# LQFP100_Breakout.net
KiCad netlist of a schematic drawn in EAGLE
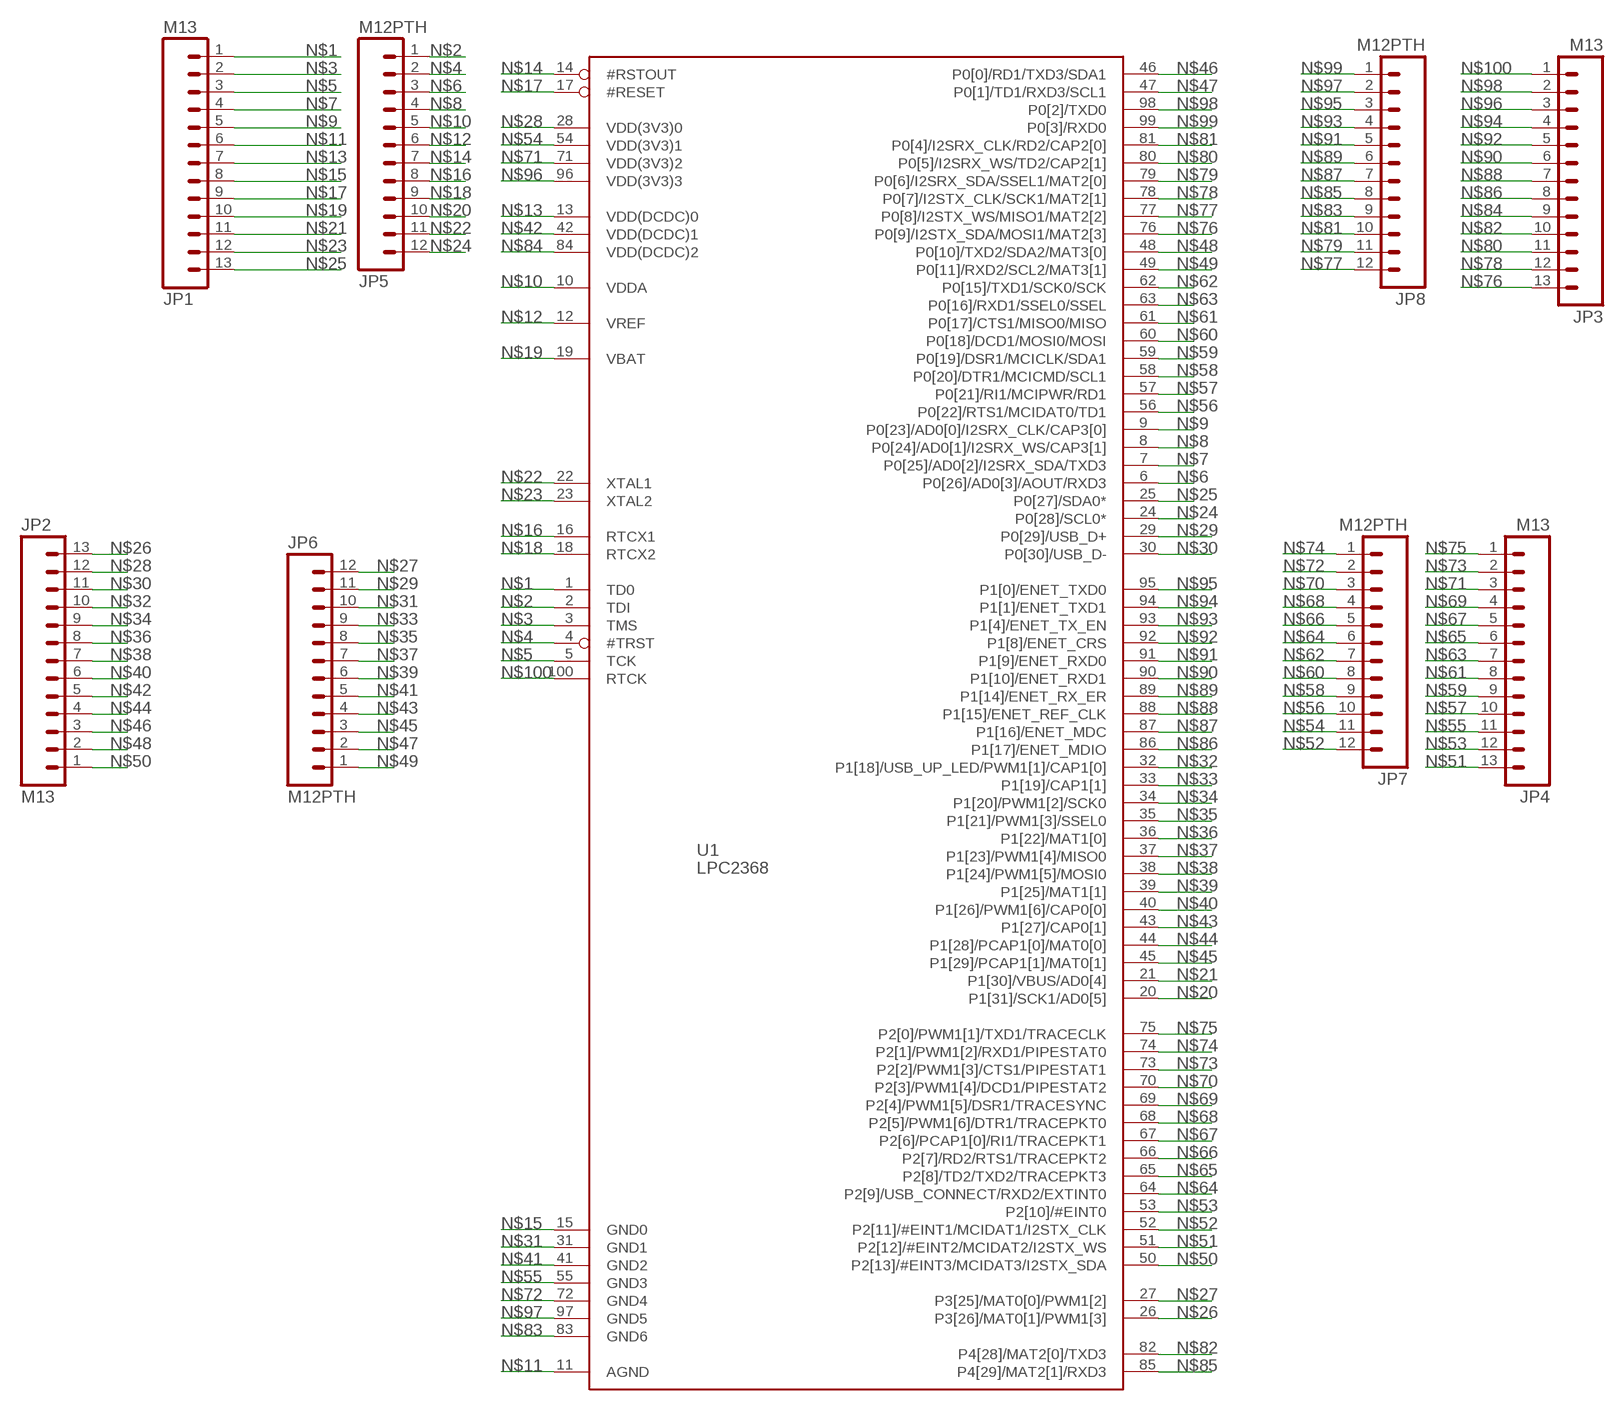
[diagram p0: schematic, sheet 1]

(export (version "E")
  (design (tool "Eeschema 10.0.6"))
  (components
    (comp (ref "JP1")
      (value "M13")
      (footprint "eagle-import:1X13")
      (libsource (lib "eagle-import") (part "M13"))
    )
    (comp (ref "JP2")
      (value "M13")
      (footprint "eagle-import:1X13")
      (libsource (lib "eagle-import") (part "M13"))
    )
    (comp (ref "JP3")
      (value "M13")
      (footprint "eagle-import:1X13")
      (libsource (lib "eagle-import") (part "M13"))
    )
    (comp (ref "JP4")
      (value "M13")
      (footprint "eagle-import:1X13")
      (libsource (lib "eagle-import") (part "M13"))
    )
    (comp (ref "JP5")
      (value "M12PTH")
      (footprint "eagle-import:1X12")
      (libsource (lib "eagle-import") (part "M12PTH"))
    )
    (comp (ref "JP6")
      (value "M12PTH")
      (footprint "eagle-import:1X12")
      (libsource (lib "eagle-import") (part "M12PTH"))
    )
    (comp (ref "JP7")
      (value "M12PTH")
      (footprint "eagle-import:1X12")
      (libsource (lib "eagle-import") (part "M12PTH"))
    )
    (comp (ref "JP8")
      (value "M12PTH")
      (footprint "eagle-import:1X12")
      (libsource (lib "eagle-import") (part "M12PTH"))
    )
    (comp (ref "U1")
      (value "LPC2368")
      (footprint "eagle-import:LQFP100")
      (libsource (lib "eagle-import") (part "LPC2368"))
    )
  )
  (nets
    (net (code "1") (name "/N$1") (class "Default")
      (node (ref "JP1") (pin "1") (pinfunction "1_1") (pintype "passive"))
      (node (ref "U1") (pin "1") (pinfunction "TD0_1") (pintype "bidirectional"))
    )
    (net (code "2") (name "/N$2") (class "Default")
      (node (ref "JP5") (pin "1") (pinfunction "1_1") (pintype "passive"))
      (node (ref "U1") (pin "2") (pinfunction "TDI_2") (pintype "bidirectional"))
    )
    (net (code "3") (name "/N$3") (class "Default")
      (node (ref "JP1") (pin "2") (pinfunction "2_2") (pintype "passive"))
      (node (ref "U1") (pin "3") (pinfunction "TMS_3") (pintype "bidirectional"))
    )
    (net (code "4") (name "/N$4") (class "Default")
      (node (ref "JP5") (pin "2") (pinfunction "2_2") (pintype "passive"))
      (node (ref "U1") (pin "4") (pinfunction "#TRST_4") (pintype "bidirectional"))
    )
    (net (code "5") (name "/N$5") (class "Default")
      (node (ref "JP1") (pin "3") (pinfunction "3_3") (pintype "passive"))
      (node (ref "U1") (pin "5") (pinfunction "TCK_5") (pintype "bidirectional"))
    )
    (net (code "6") (name "/N$6") (class "Default")
      (node (ref "JP5") (pin "3") (pinfunction "3_3") (pintype "passive"))
      (node (ref "U1") (pin "6") (pinfunction "P0[26]/AD0[3]/AOUT/RXD3_6") (pintype "bidirectional"))
    )
    (net (code "7") (name "/N$7") (class "Default")
      (node (ref "JP1") (pin "4") (pinfunction "4_4") (pintype "passive"))
      (node (ref "U1") (pin "7") (pinfunction "P0[25]/AD0[2]/I2SRX_SDA/TXD3_7") (pintype "bidirectional"))
    )
    (net (code "8") (name "/N$8") (class "Default")
      (node (ref "JP5") (pin "4") (pinfunction "4_4") (pintype "passive"))
      (node (ref "U1") (pin "8") (pinfunction "P0[24]/AD0[1]/I2SRX_WS/CAP3[1]_8") (pintype "bidirectional"))
    )
    (net (code "9") (name "/N$9") (class "Default")
      (node (ref "JP1") (pin "5") (pinfunction "5_5") (pintype "passive"))
      (node (ref "U1") (pin "9") (pinfunction "P0[23]/AD0[0]/I2SRX_CLK/CAP3[0]_9") (pintype "bidirectional"))
    )
    (net (code "10") (name "/N$10") (class "Default")
      (node (ref "JP5") (pin "5") (pinfunction "5_5") (pintype "passive"))
      (node (ref "U1") (pin "10") (pinfunction "VDDA_10") (pintype "bidirectional"))
    )
    (net (code "11") (name "/N$11") (class "Default")
      (node (ref "JP1") (pin "6") (pinfunction "6_6") (pintype "passive"))
      (node (ref "U1") (pin "11") (pinfunction "AGND_11") (pintype "bidirectional"))
    )
    (net (code "12") (name "/N$12") (class "Default")
      (node (ref "JP5") (pin "6") (pinfunction "6_6") (pintype "passive"))
      (node (ref "U1") (pin "12") (pinfunction "VREF_12") (pintype "bidirectional"))
    )
    (net (code "13") (name "/N$13") (class "Default")
      (node (ref "JP1") (pin "7") (pinfunction "7_7") (pintype "passive"))
      (node (ref "U1") (pin "13") (pinfunction "VDD(DCDC)0_13") (pintype "bidirectional"))
    )
    (net (code "14") (name "/N$14") (class "Default")
      (node (ref "JP5") (pin "7") (pinfunction "7_7") (pintype "passive"))
      (node (ref "U1") (pin "14") (pinfunction "#RSTOUT_14") (pintype "bidirectional"))
    )
    (net (code "15") (name "/N$15") (class "Default")
      (node (ref "JP1") (pin "8") (pinfunction "8_8") (pintype "passive"))
      (node (ref "U1") (pin "15") (pinfunction "GND0_15") (pintype "bidirectional"))
    )
    (net (code "16") (name "/N$16") (class "Default")
      (node (ref "JP5") (pin "8") (pinfunction "8_8") (pintype "passive"))
      (node (ref "U1") (pin "16") (pinfunction "RTCX1_16") (pintype "bidirectional"))
    )
    (net (code "17") (name "/N$17") (class "Default")
      (node (ref "JP1") (pin "9") (pinfunction "9_9") (pintype "passive"))
      (node (ref "U1") (pin "17") (pinfunction "#RESET_17") (pintype "bidirectional"))
    )
    (net (code "18") (name "/N$18") (class "Default")
      (node (ref "JP5") (pin "9") (pinfunction "9_9") (pintype "passive"))
      (node (ref "U1") (pin "18") (pinfunction "RTCX2_18") (pintype "bidirectional"))
    )
    (net (code "19") (name "/N$19") (class "Default")
      (node (ref "JP1") (pin "10") (pinfunction "10_10") (pintype "passive"))
      (node (ref "U1") (pin "19") (pinfunction "VBAT_19") (pintype "bidirectional"))
    )
    (net (code "20") (name "/N$20") (class "Default")
      (node (ref "JP5") (pin "10") (pinfunction "10_10") (pintype "passive"))
      (node (ref "U1") (pin "20") (pinfunction "P1[31]/SCK1/AD0[5]_20") (pintype "bidirectional"))
    )
    (net (code "21") (name "/N$21") (class "Default")
      (node (ref "JP1") (pin "11") (pinfunction "11_11") (pintype "passive"))
      (node (ref "U1") (pin "21") (pinfunction "P1[30]/VBUS/AD0[4]_21") (pintype "bidirectional"))
    )
    (net (code "22") (name "/N$22") (class "Default")
      (node (ref "JP5") (pin "11") (pinfunction "11_11") (pintype "passive"))
      (node (ref "U1") (pin "22") (pinfunction "XTAL1_22") (pintype "bidirectional"))
    )
    (net (code "23") (name "/N$23") (class "Default")
      (node (ref "JP1") (pin "12") (pinfunction "12_12") (pintype "passive"))
      (node (ref "U1") (pin "23") (pinfunction "XTAL2_23") (pintype "bidirectional"))
    )
    (net (code "24") (name "/N$24") (class "Default")
      (node (ref "JP5") (pin "12") (pinfunction "12_12") (pintype "passive"))
      (node (ref "U1") (pin "24") (pinfunction "P0[28]/SCL0*_24") (pintype "bidirectional"))
    )
    (net (code "25") (name "/N$25") (class "Default")
      (node (ref "JP1") (pin "13") (pinfunction "13_13") (pintype "passive"))
      (node (ref "U1") (pin "25") (pinfunction "P0[27]/SDA0*_25") (pintype "bidirectional"))
    )
    (net (code "26") (name "/N$26") (class "Default")
      (node (ref "JP2") (pin "13") (pinfunction "13_13") (pintype "passive"))
      (node (ref "U1") (pin "26") (pinfunction "P3[26]/MAT0[1]/PWM1[3]_26") (pintype "bidirectional"))
    )
    (net (code "27") (name "/N$27") (class "Default")
      (node (ref "JP6") (pin "12") (pinfunction "12_12") (pintype "passive"))
      (node (ref "U1") (pin "27") (pinfunction "P3[25]/MAT0[0]/PWM1[2]_27") (pintype "bidirectional"))
    )
    (net (code "28") (name "/N$28") (class "Default")
      (node (ref "JP2") (pin "12") (pinfunction "12_12") (pintype "passive"))
      (node (ref "U1") (pin "28") (pinfunction "VDD(3V3)0_28") (pintype "bidirectional"))
    )
    (net (code "29") (name "/N$29") (class "Default")
      (node (ref "JP6") (pin "11") (pinfunction "11_11") (pintype "passive"))
      (node (ref "U1") (pin "29") (pinfunction "P0[29]/USB_D+_29") (pintype "bidirectional"))
    )
    (net (code "30") (name "/N$30") (class "Default")
      (node (ref "JP2") (pin "11") (pinfunction "11_11") (pintype "passive"))
      (node (ref "U1") (pin "30") (pinfunction "P0[30]/USB_D-_30") (pintype "bidirectional"))
    )
    (net (code "31") (name "/N$31") (class "Default")
      (node (ref "JP6") (pin "10") (pinfunction "10_10") (pintype "passive"))
      (node (ref "U1") (pin "31") (pinfunction "GND1_31") (pintype "bidirectional"))
    )
    (net (code "32") (name "/N$32") (class "Default")
      (node (ref "JP2") (pin "10") (pinfunction "10_10") (pintype "passive"))
      (node (ref "U1") (pin "32") (pinfunction "P1[18]/USB_UP_LED/PWM1[1]/CAP1[0]_32") (pintype "bidirectional"))
    )
    (net (code "33") (name "/N$33") (class "Default")
      (node (ref "JP6") (pin "9") (pinfunction "9_9") (pintype "passive"))
      (node (ref "U1") (pin "33") (pinfunction "P1[19]/CAP1[1]_33") (pintype "bidirectional"))
    )
    (net (code "34") (name "/N$34") (class "Default")
      (node (ref "JP2") (pin "9") (pinfunction "9_9") (pintype "passive"))
      (node (ref "U1") (pin "34") (pinfunction "P1[20]/PWM1[2]/SCK0_34") (pintype "bidirectional"))
    )
    (net (code "35") (name "/N$35") (class "Default")
      (node (ref "JP6") (pin "8") (pinfunction "8_8") (pintype "passive"))
      (node (ref "U1") (pin "35") (pinfunction "P1[21]/PWM1[3]/SSEL0_35") (pintype "bidirectional"))
    )
    (net (code "36") (name "/N$36") (class "Default")
      (node (ref "JP2") (pin "8") (pinfunction "8_8") (pintype "passive"))
      (node (ref "U1") (pin "36") (pinfunction "P1[22]/MAT1[0]_36") (pintype "bidirectional"))
    )
    (net (code "37") (name "/N$37") (class "Default")
      (node (ref "JP6") (pin "7") (pinfunction "7_7") (pintype "passive"))
      (node (ref "U1") (pin "37") (pinfunction "P1[23]/PWM1[4]/MISO0_37") (pintype "bidirectional"))
    )
    (net (code "38") (name "/N$38") (class "Default")
      (node (ref "JP2") (pin "7") (pinfunction "7_7") (pintype "passive"))
      (node (ref "U1") (pin "38") (pinfunction "P1[24]/PWM1[5]/MOSI0_38") (pintype "bidirectional"))
    )
    (net (code "39") (name "/N$39") (class "Default")
      (node (ref "JP6") (pin "6") (pinfunction "6_6") (pintype "passive"))
      (node (ref "U1") (pin "39") (pinfunction "P1[25]/MAT1[1]_39") (pintype "bidirectional"))
    )
    (net (code "40") (name "/N$40") (class "Default")
      (node (ref "JP2") (pin "6") (pinfunction "6_6") (pintype "passive"))
      (node (ref "U1") (pin "40") (pinfunction "P1[26]/PWM1[6]/CAP0[0]_40") (pintype "bidirectional"))
    )
    (net (code "41") (name "/N$41") (class "Default")
      (node (ref "JP6") (pin "5") (pinfunction "5_5") (pintype "passive"))
      (node (ref "U1") (pin "41") (pinfunction "GND2_41") (pintype "bidirectional"))
    )
    (net (code "42") (name "/N$42") (class "Default")
      (node (ref "JP2") (pin "5") (pinfunction "5_5") (pintype "passive"))
      (node (ref "U1") (pin "42") (pinfunction "VDD(DCDC)1_42") (pintype "bidirectional"))
    )
    (net (code "43") (name "/N$43") (class "Default")
      (node (ref "JP6") (pin "4") (pinfunction "4_4") (pintype "passive"))
      (node (ref "U1") (pin "43") (pinfunction "P1[27]/CAP0[1]_43") (pintype "bidirectional"))
    )
    (net (code "44") (name "/N$44") (class "Default")
      (node (ref "JP2") (pin "4") (pinfunction "4_4") (pintype "passive"))
      (node (ref "U1") (pin "44") (pinfunction "P1[28]/PCAP1[0]/MAT0[0]_44") (pintype "bidirectional"))
    )
    (net (code "45") (name "/N$45") (class "Default")
      (node (ref "JP6") (pin "3") (pinfunction "3_3") (pintype "passive"))
      (node (ref "U1") (pin "45") (pinfunction "P1[29]/PCAP1[1]/MAT0[1]_45") (pintype "bidirectional"))
    )
    (net (code "46") (name "/N$46") (class "Default")
      (node (ref "JP2") (pin "3") (pinfunction "3_3") (pintype "passive"))
      (node (ref "U1") (pin "46") (pinfunction "P0[0]/RD1/TXD3/SDA1_46") (pintype "bidirectional"))
    )
    (net (code "47") (name "/N$47") (class "Default")
      (node (ref "JP6") (pin "2") (pinfunction "2_2") (pintype "passive"))
      (node (ref "U1") (pin "47") (pinfunction "P0[1]/TD1/RXD3/SCL1_47") (pintype "bidirectional"))
    )
    (net (code "48") (name "/N$48") (class "Default")
      (node (ref "JP2") (pin "2") (pinfunction "2_2") (pintype "passive"))
      (node (ref "U1") (pin "48") (pinfunction "P0[10]/TXD2/SDA2/MAT3[0]_48") (pintype "bidirectional"))
    )
    (net (code "49") (name "/N$49") (class "Default")
      (node (ref "JP6") (pin "1") (pinfunction "1_1") (pintype "passive"))
      (node (ref "U1") (pin "49") (pinfunction "P0[11]/RXD2/SCL2/MAT3[1]_49") (pintype "bidirectional"))
    )
    (net (code "50") (name "/N$50") (class "Default")
      (node (ref "JP2") (pin "1") (pinfunction "1_1") (pintype "passive"))
      (node (ref "U1") (pin "50") (pinfunction "P2[13]/#EINT3/MCIDAT3/I2STX_SDA_50") (pintype "bidirectional"))
    )
    (net (code "51") (name "/N$51") (class "Default")
      (node (ref "JP4") (pin "13") (pinfunction "13_13") (pintype "passive"))
      (node (ref "U1") (pin "51") (pinfunction "P2[12]/#EINT2/MCIDAT2/I2STX_WS_51") (pintype "bidirectional"))
    )
    (net (code "52") (name "/N$52") (class "Default")
      (node (ref "JP7") (pin "12") (pinfunction "12_12") (pintype "passive"))
      (node (ref "U1") (pin "52") (pinfunction "P2[11]/#EINT1/MCIDAT1/I2STX_CLK_52") (pintype "bidirectional"))
    )
    (net (code "53") (name "/N$53") (class "Default")
      (node (ref "JP4") (pin "12") (pinfunction "12_12") (pintype "passive"))
      (node (ref "U1") (pin "53") (pinfunction "P2[10]/#EINT0_53") (pintype "bidirectional"))
    )
    (net (code "54") (name "/N$54") (class "Default")
      (node (ref "JP7") (pin "11") (pinfunction "11_11") (pintype "passive"))
      (node (ref "U1") (pin "54") (pinfunction "VDD(3V3)1_54") (pintype "bidirectional"))
    )
    (net (code "55") (name "/N$55") (class "Default")
      (node (ref "JP4") (pin "11") (pinfunction "11_11") (pintype "passive"))
      (node (ref "U1") (pin "55") (pinfunction "GND3_55") (pintype "bidirectional"))
    )
    (net (code "56") (name "/N$56") (class "Default")
      (node (ref "JP7") (pin "10") (pinfunction "10_10") (pintype "passive"))
      (node (ref "U1") (pin "56") (pinfunction "P0[22]/RTS1/MCIDAT0/TD1_56") (pintype "bidirectional"))
    )
    (net (code "57") (name "/N$57") (class "Default")
      (node (ref "JP4") (pin "10") (pinfunction "10_10") (pintype "passive"))
      (node (ref "U1") (pin "57") (pinfunction "P0[21]/RI1/MCIPWR/RD1_57") (pintype "bidirectional"))
    )
    (net (code "58") (name "/N$58") (class "Default")
      (node (ref "JP7") (pin "9") (pinfunction "9_9") (pintype "passive"))
      (node (ref "U1") (pin "58") (pinfunction "P0[20]/DTR1/MCICMD/SCL1_58") (pintype "bidirectional"))
    )
    (net (code "59") (name "/N$59") (class "Default")
      (node (ref "JP4") (pin "9") (pinfunction "9_9") (pintype "passive"))
      (node (ref "U1") (pin "59") (pinfunction "P0[19]/DSR1/MCICLK/SDA1_59") (pintype "bidirectional"))
    )
    (net (code "60") (name "/N$60") (class "Default")
      (node (ref "JP7") (pin "8") (pinfunction "8_8") (pintype "passive"))
      (node (ref "U1") (pin "60") (pinfunction "P0[18]/DCD1/MOSI0/MOSI_60") (pintype "bidirectional"))
    )
    (net (code "61") (name "/N$61") (class "Default")
      (node (ref "JP4") (pin "8") (pinfunction "8_8") (pintype "passive"))
      (node (ref "U1") (pin "61") (pinfunction "P0[17]/CTS1/MISO0/MISO_61") (pintype "bidirectional"))
    )
    (net (code "62") (name "/N$62") (class "Default")
      (node (ref "JP7") (pin "7") (pinfunction "7_7") (pintype "passive"))
      (node (ref "U1") (pin "62") (pinfunction "P0[15]/TXD1/SCK0/SCK_62") (pintype "bidirectional"))
    )
    (net (code "63") (name "/N$63") (class "Default")
      (node (ref "JP4") (pin "7") (pinfunction "7_7") (pintype "passive"))
      (node (ref "U1") (pin "63") (pinfunction "P0[16]/RXD1/SSEL0/SSEL_63") (pintype "bidirectional"))
    )
    (net (code "64") (name "/N$64") (class "Default")
      (node (ref "JP7") (pin "6") (pinfunction "6_6") (pintype "passive"))
      (node (ref "U1") (pin "64") (pinfunction "P2[9]/USB_CONNECT/RXD2/EXTINT0_64") (pintype "bidirectional"))
    )
    (net (code "65") (name "/N$65") (class "Default")
      (node (ref "JP4") (pin "6") (pinfunction "6_6") (pintype "passive"))
      (node (ref "U1") (pin "65") (pinfunction "P2[8]/TD2/TXD2/TRACEPKT3_65") (pintype "bidirectional"))
    )
    (net (code "66") (name "/N$66") (class "Default")
      (node (ref "JP7") (pin "5") (pinfunction "5_5") (pintype "passive"))
      (node (ref "U1") (pin "66") (pinfunction "P2[7]/RD2/RTS1/TRACEPKT2_66") (pintype "bidirectional"))
    )
    (net (code "67") (name "/N$67") (class "Default")
      (node (ref "JP4") (pin "5") (pinfunction "5_5") (pintype "passive"))
      (node (ref "U1") (pin "67") (pinfunction "P2[6]/PCAP1[0]/RI1/TRACEPKT1_67") (pintype "bidirectional"))
    )
    (net (code "68") (name "/N$68") (class "Default")
      (node (ref "JP7") (pin "4") (pinfunction "4_4") (pintype "passive"))
      (node (ref "U1") (pin "68") (pinfunction "P2[5]/PWM1[6]/DTR1/TRACEPKT0_68") (pintype "bidirectional"))
    )
    (net (code "69") (name "/N$69") (class "Default")
      (node (ref "JP4") (pin "4") (pinfunction "4_4") (pintype "passive"))
      (node (ref "U1") (pin "69") (pinfunction "P2[4]/PWM1[5]/DSR1/TRACESYNC_69") (pintype "bidirectional"))
    )
    (net (code "70") (name "/N$70") (class "Default")
      (node (ref "JP7") (pin "3") (pinfunction "3_3") (pintype "passive"))
      (node (ref "U1") (pin "70") (pinfunction "P2[3]/PWM1[4]/DCD1/PIPESTAT2_70") (pintype "bidirectional"))
    )
    (net (code "71") (name "/N$71") (class "Default")
      (node (ref "JP4") (pin "3") (pinfunction "3_3") (pintype "passive"))
      (node (ref "U1") (pin "71") (pinfunction "VDD(3V3)2_71") (pintype "bidirectional"))
    )
    (net (code "72") (name "/N$72") (class "Default")
      (node (ref "JP7") (pin "2") (pinfunction "2_2") (pintype "passive"))
      (node (ref "U1") (pin "72") (pinfunction "GND4_72") (pintype "bidirectional"))
    )
    (net (code "73") (name "/N$73") (class "Default")
      (node (ref "JP4") (pin "2") (pinfunction "2_2") (pintype "passive"))
      (node (ref "U1") (pin "73") (pinfunction "P2[2]/PWM1[3]/CTS1/PIPESTAT1_73") (pintype "bidirectional"))
    )
    (net (code "74") (name "/N$74") (class "Default")
      (node (ref "JP7") (pin "1") (pinfunction "1_1") (pintype "passive"))
      (node (ref "U1") (pin "74") (pinfunction "P2[1]/PWM1[2]/RXD1/PIPESTAT0_74") (pintype "bidirectional"))
    )
    (net (code "75") (name "/N$75") (class "Default")
      (node (ref "JP4") (pin "1") (pinfunction "1_1") (pintype "passive"))
      (node (ref "U1") (pin "75") (pinfunction "P2[0]/PWM1[1]/TXD1/TRACECLK_75") (pintype "bidirectional"))
    )
    (net (code "76") (name "/N$76") (class "Default")
      (node (ref "JP3") (pin "13") (pinfunction "13_13") (pintype "passive"))
      (node (ref "U1") (pin "76") (pinfunction "P0[9]/I2STX_SDA/MOSI1/MAT2[3]_76") (pintype "bidirectional"))
    )
    (net (code "77") (name "/N$77") (class "Default")
      (node (ref "JP8") (pin "12") (pinfunction "12_12") (pintype "passive"))
      (node (ref "U1") (pin "77") (pinfunction "P0[8]/I2STX_WS/MISO1/MAT2[2]_77") (pintype "bidirectional"))
    )
    (net (code "78") (name "/N$78") (class "Default")
      (node (ref "JP3") (pin "12") (pinfunction "12_12") (pintype "passive"))
      (node (ref "U1") (pin "78") (pinfunction "P0[7]/I2STX_CLK/SCK1/MAT2[1]_78") (pintype "bidirectional"))
    )
    (net (code "79") (name "/N$79") (class "Default")
      (node (ref "JP8") (pin "11") (pinfunction "11_11") (pintype "passive"))
      (node (ref "U1") (pin "79") (pinfunction "P0[6]/I2SRX_SDA/SSEL1/MAT2[0]_79") (pintype "bidirectional"))
    )
    (net (code "80") (name "/N$80") (class "Default")
      (node (ref "JP3") (pin "11") (pinfunction "11_11") (pintype "passive"))
      (node (ref "U1") (pin "80") (pinfunction "P0[5]/I2SRX_WS/TD2/CAP2[1]_80") (pintype "bidirectional"))
    )
    (net (code "81") (name "/N$81") (class "Default")
      (node (ref "JP8") (pin "10") (pinfunction "10_10") (pintype "passive"))
      (node (ref "U1") (pin "81") (pinfunction "P0[4]/I2SRX_CLK/RD2/CAP2[0]_81") (pintype "bidirectional"))
    )
    (net (code "82") (name "/N$82") (class "Default")
      (node (ref "JP3") (pin "10") (pinfunction "10_10") (pintype "passive"))
      (node (ref "U1") (pin "82") (pinfunction "P4[28]/MAT2[0]/TXD3_82") (pintype "bidirectional"))
    )
    (net (code "83") (name "/N$83") (class "Default")
      (node (ref "JP8") (pin "9") (pinfunction "9_9") (pintype "passive"))
      (node (ref "U1") (pin "83") (pinfunction "GND6_83") (pintype "bidirectional"))
    )
    (net (code "84") (name "/N$84") (class "Default")
      (node (ref "JP3") (pin "9") (pinfunction "9_9") (pintype "passive"))
      (node (ref "U1") (pin "84") (pinfunction "VDD(DCDC)2_84") (pintype "bidirectional"))
    )
    (net (code "85") (name "/N$85") (class "Default")
      (node (ref "JP8") (pin "8") (pinfunction "8_8") (pintype "passive"))
      (node (ref "U1") (pin "85") (pinfunction "P4[29]/MAT2[1]/RXD3_85") (pintype "bidirectional"))
    )
    (net (code "86") (name "/N$86") (class "Default")
      (node (ref "JP3") (pin "8") (pinfunction "8_8") (pintype "passive"))
      (node (ref "U1") (pin "86") (pinfunction "P1[17]/ENET_MDIO_86") (pintype "bidirectional"))
    )
    (net (code "87") (name "/N$87") (class "Default")
      (node (ref "JP8") (pin "7") (pinfunction "7_7") (pintype "passive"))
      (node (ref "U1") (pin "87") (pinfunction "P1[16]/ENET_MDC_87") (pintype "bidirectional"))
    )
    (net (code "88") (name "/N$88") (class "Default")
      (node (ref "JP3") (pin "7") (pinfunction "7_7") (pintype "passive"))
      (node (ref "U1") (pin "88") (pinfunction "P1[15]/ENET_REF_CLK_88") (pintype "bidirectional"))
    )
    (net (code "89") (name "/N$89") (class "Default")
      (node (ref "JP8") (pin "6") (pinfunction "6_6") (pintype "passive"))
      (node (ref "U1") (pin "89") (pinfunction "P1[14]/ENET_RX_ER_89") (pintype "bidirectional"))
    )
    (net (code "90") (name "/N$90") (class "Default")
      (node (ref "JP3") (pin "6") (pinfunction "6_6") (pintype "passive"))
      (node (ref "U1") (pin "90") (pinfunction "P1[10]/ENET_RXD1_90") (pintype "bidirectional"))
    )
    (net (code "91") (name "/N$91") (class "Default")
      (node (ref "JP8") (pin "5") (pinfunction "5_5") (pintype "passive"))
      (node (ref "U1") (pin "91") (pinfunction "P1[9]/ENET_RXD0_91") (pintype "bidirectional"))
    )
    (net (code "92") (name "/N$92") (class "Default")
      (node (ref "JP3") (pin "5") (pinfunction "5_5") (pintype "passive"))
      (node (ref "U1") (pin "92") (pinfunction "P1[8]/ENET_CRS_92") (pintype "bidirectional"))
    )
    (net (code "93") (name "/N$93") (class "Default")
      (node (ref "JP8") (pin "4") (pinfunction "4_4") (pintype "passive"))
      (node (ref "U1") (pin "93") (pinfunction "P1[4]/ENET_TX_EN_93") (pintype "bidirectional"))
    )
    (net (code "94") (name "/N$94") (class "Default")
      (node (ref "JP3") (pin "4") (pinfunction "4_4") (pintype "passive"))
      (node (ref "U1") (pin "94") (pinfunction "P1[1]/ENET_TXD1_94") (pintype "bidirectional"))
    )
    (net (code "95") (name "/N$95") (class "Default")
      (node (ref "JP8") (pin "3") (pinfunction "3_3") (pintype "passive"))
      (node (ref "U1") (pin "95") (pinfunction "P1[0]/ENET_TXD0_95") (pintype "bidirectional"))
    )
    (net (code "96") (name "/N$96") (class "Default")
      (node (ref "JP3") (pin "3") (pinfunction "3_3") (pintype "passive"))
      (node (ref "U1") (pin "96") (pinfunction "VDD(3V3)3_96") (pintype "bidirectional"))
    )
    (net (code "97") (name "/N$97") (class "Default")
      (node (ref "JP8") (pin "2") (pinfunction "2_2") (pintype "passive"))
      (node (ref "U1") (pin "97") (pinfunction "GND5_97") (pintype "bidirectional"))
    )
    (net (code "98") (name "/N$98") (class "Default")
      (node (ref "JP3") (pin "2") (pinfunction "2_2") (pintype "passive"))
      (node (ref "U1") (pin "98") (pinfunction "P0[2]/TXD0_98") (pintype "bidirectional"))
    )
    (net (code "99") (name "/N$99") (class "Default")
      (node (ref "JP8") (pin "1") (pinfunction "1_1") (pintype "passive"))
      (node (ref "U1") (pin "99") (pinfunction "P0[3]/RXD0_99") (pintype "bidirectional"))
    )
    (net (code "100") (name "/N$100") (class "Default")
      (node (ref "JP3") (pin "1") (pinfunction "1_1") (pintype "passive"))
      (node (ref "U1") (pin "100") (pinfunction "RTCK_100") (pintype "bidirectional"))
    )
  )
)
